# DC075B_CW_OUTPUTS.net
KiCad netlist of a schematic drawn in Altium Designer
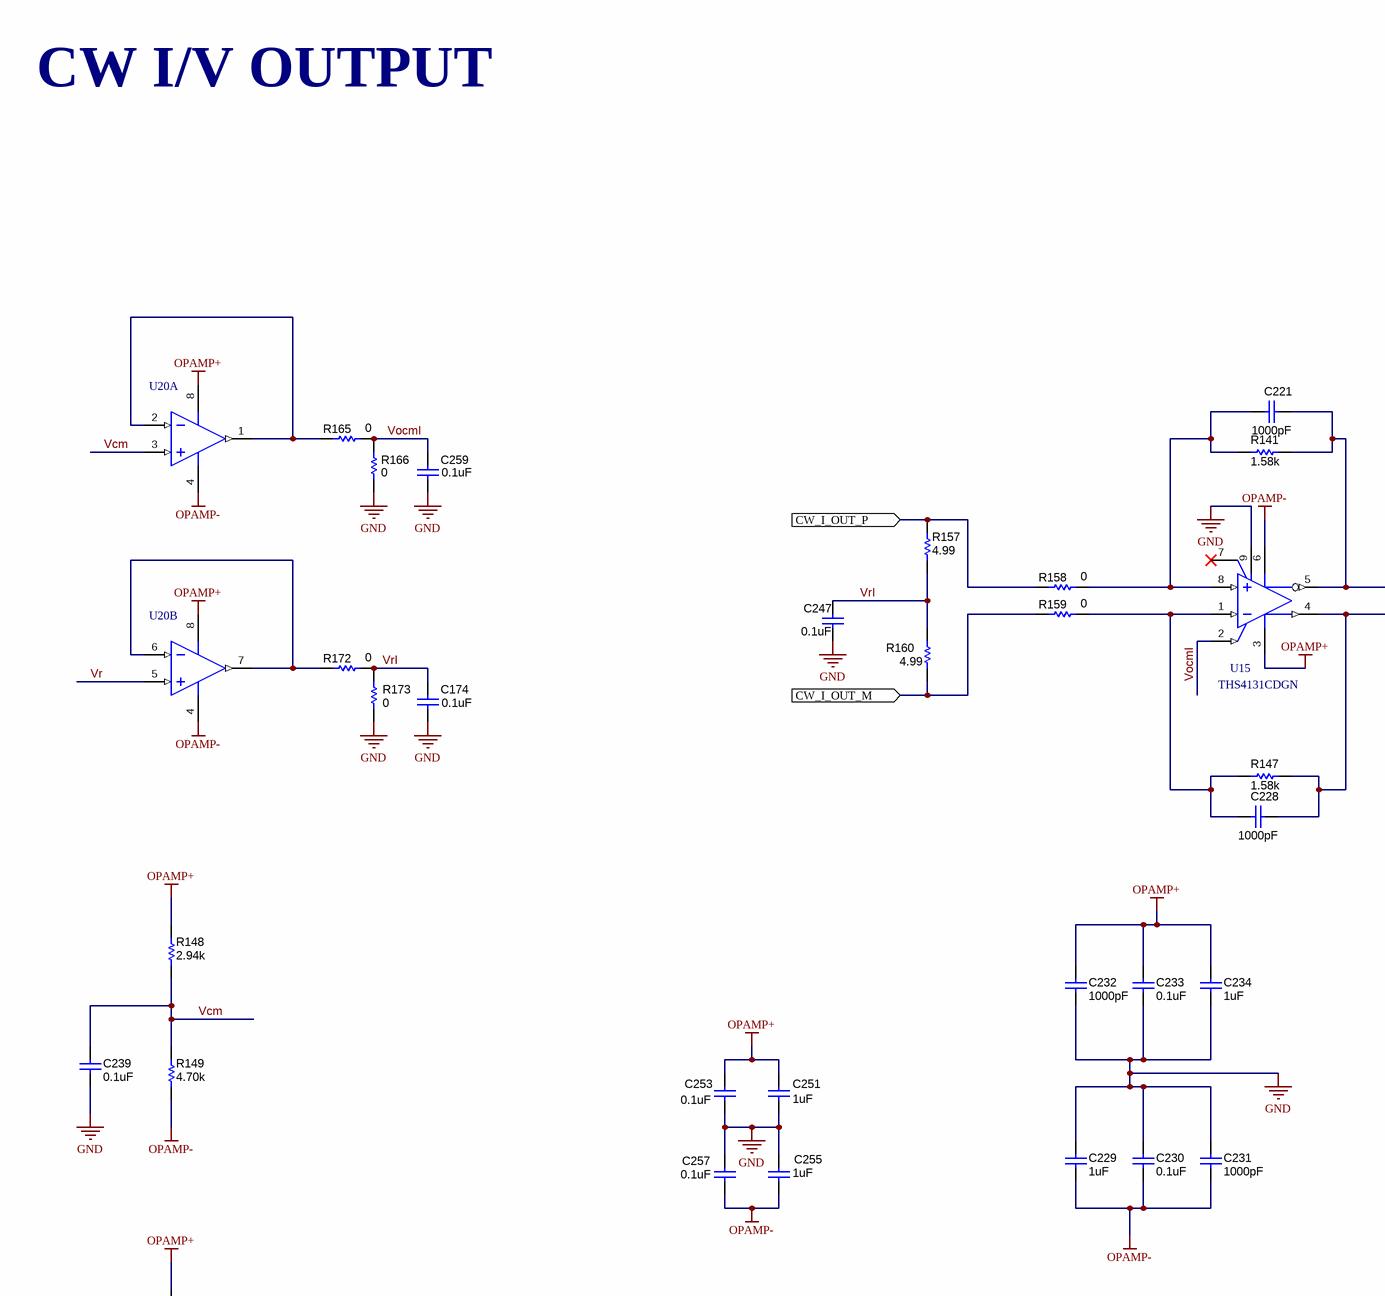
[diagram p0: DC075B_CW_OUTPUTS.SchDoc, top left]
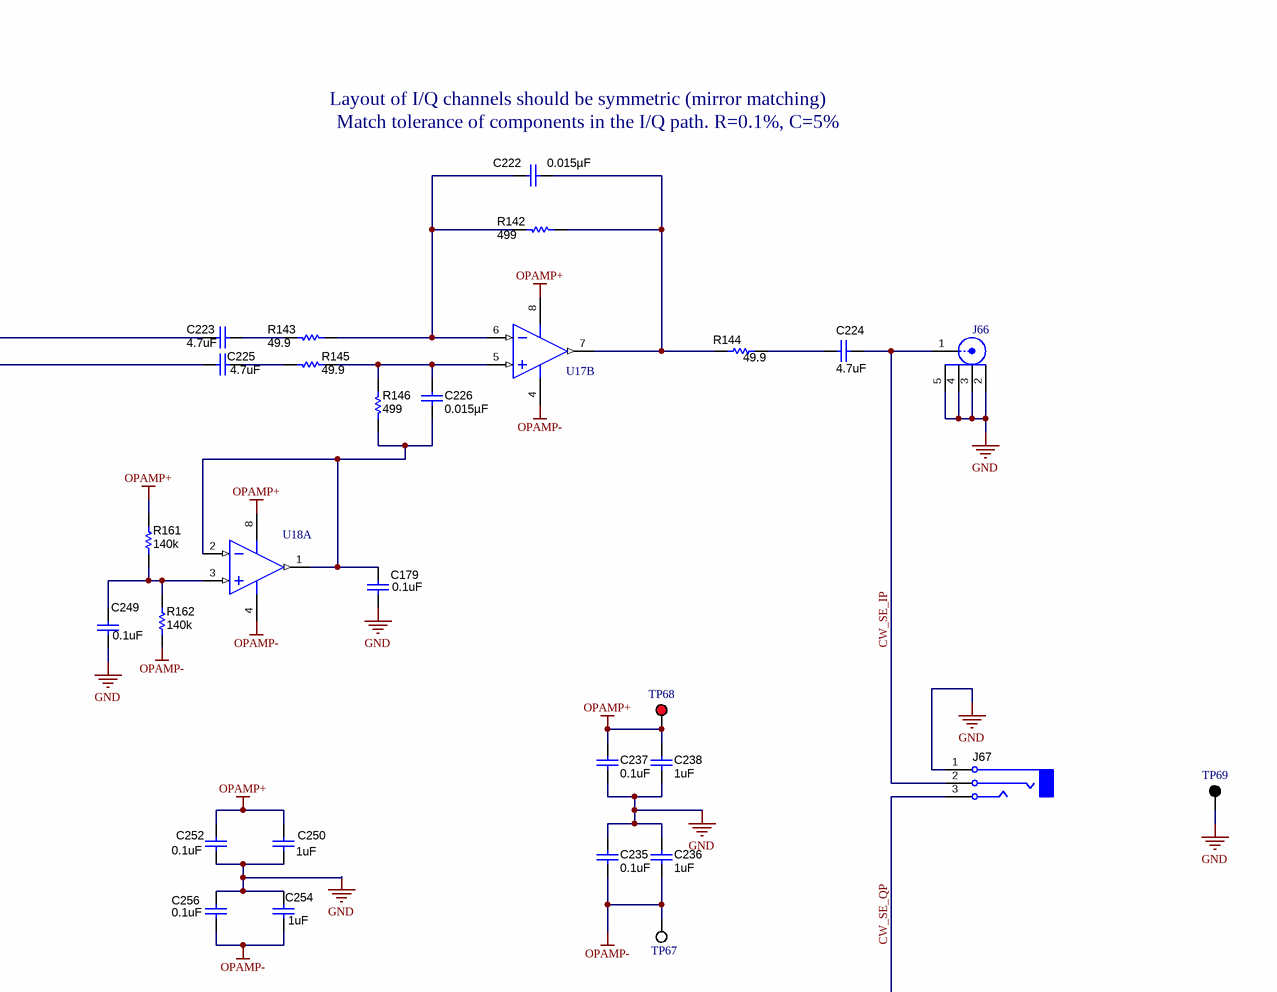
[diagram p1: DC075B_CW_OUTPUTS.SchDoc, top right]
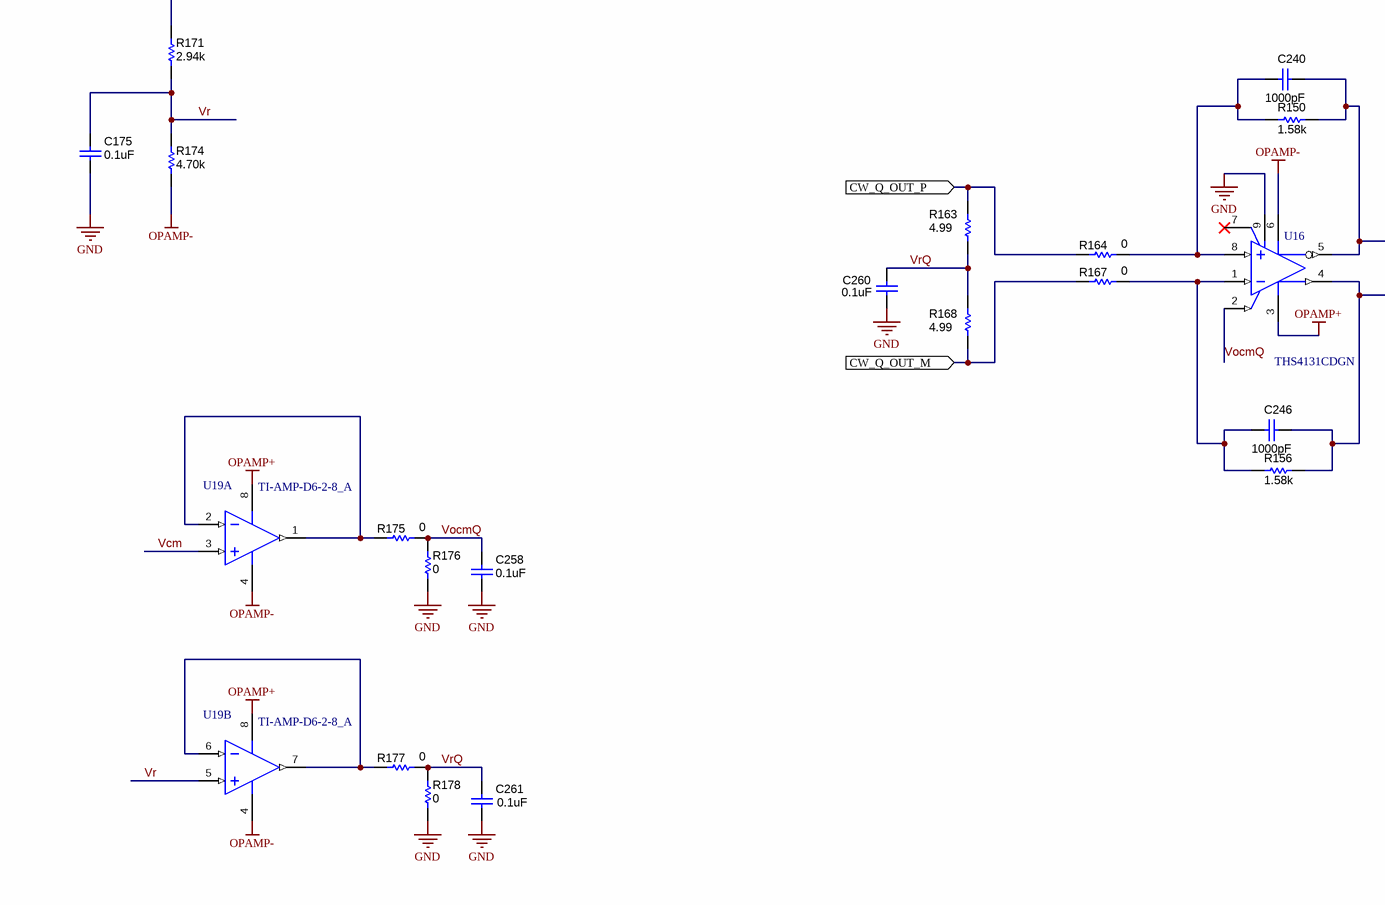
[diagram p2: DC075B_CW_OUTPUTS.SchDoc, bottom left]
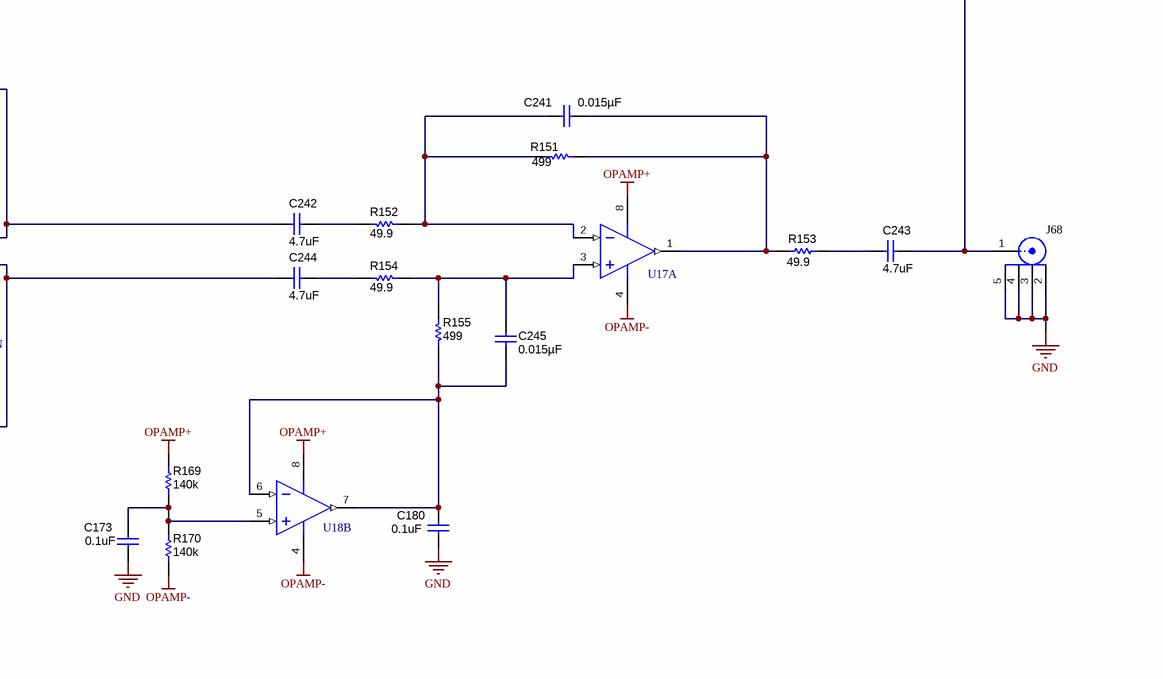
[diagram p3: DC075B_CW_OUTPUTS.SchDoc, bottom right]

(export (version "E")
  (design (tool "Eeschema 10.0.6"))
  (components
    (comp (ref "C173")
      (value "0.1uF")
      (footprint "0402")
      (description "CAP, CERM, 0.1 uF, 16 V, +/- 10%, X7R, 0402")
      (fields (field (name "PARTNUMBER") "GRM155R71C104KA88D") (field (name "MANUFACTURER") "MuRata"))
      (libsource (lib "Altium Vault - TI") (part "Capacitor"))
    )
    (comp (ref "C174")
      (value "0.1uF")
      (footprint "0402")
      (description "CAP, CERM, 0.1 uF, 16 V, +/- 10%, X7R, 0402")
      (fields (field (name "PARTNUMBER") "GRM155R71C104KA88D") (field (name "MANUFACTURER") "MuRata"))
      (libsource (lib "Altium Vault - TI") (part "Capacitor"))
    )
    (comp (ref "C175")
      (value "0.1uF")
      (footprint "0402")
      (description "CAP, CERM, 0.1 uF, 16 V, +/- 10%, X7R, 0402")
      (fields (field (name "PARTNUMBER") "GRM155R71C104KA88D") (field (name "MANUFACTURER") "MuRata"))
      (libsource (lib "Altium Vault - TI") (part "Capacitor"))
    )
    (comp (ref "C179")
      (value "0.1uF")
      (footprint "0402")
      (description "CAP, CERM, 0.1 uF, 16 V, +/- 10%, X7R, 0402")
      (fields (field (name "PARTNUMBER") "GRM155R71C104KA88D") (field (name "MANUFACTURER") "MuRata"))
      (libsource (lib "Altium Vault - TI") (part "Capacitor"))
    )
    (comp (ref "C180")
      (value "0.1uF")
      (footprint "0402")
      (description "CAP, CERM, 0.1 uF, 16 V, +/- 10%, X7R, 0402")
      (fields (field (name "PARTNUMBER") "GRM155R71C104KA88D") (field (name "MANUFACTURER") "MuRata"))
      (libsource (lib "Altium Vault - TI") (part "Capacitor"))
    )
    (comp (ref "C221")
      (value "885012205044")
      (footprint "0402")
      (description "CAP, CERM, 1000 pF, 25 V, +/- 10%, X7R, 0402")
      (fields (field (name "MANUFACTURER") "Wurth Elektronik") (field (name "VALUEDISPLAYED") "1000pF"))
      (libsource (lib "Altium Vault - TI") (part "CMP-0006229-2"))
    )
    (comp (ref "C222")
      (value "C0402C153J4RAC7867")
      (footprint "0402")
      (description "CAP, CERM, 0.015 µF, 16 V,+/- 5%, X7R, 0402")
      (fields (field (name "VALUEDISPLAYED") "0.015µF") (field (name "MANUFACTURER") "Kemet"))
      (libsource (lib "Altium Vault - TI") (part "Capacitor"))
    )
    (comp (ref "C223")
      (value "Capacitor")
      (footprint "0603")
      (description "CAP, CERM, 4.7 uF, 10 V, +/- 10%, X5R, 0603")
      (fields
        (field (name "PARTNUMBER") "C0603C475K8PACTU")
        (field (name "VALUEDISPLAYED") "4.7uF")
        (field (name "MANUFACTURER") "Kemet")
      )
      (libsource (lib "Altium Vault - TI") (part "Capacitor"))
    )
    (comp (ref "C224")
      (value "Capacitor")
      (footprint "0603")
      (description "CAP, CERM, 4.7 uF, 10 V, +/- 10%, X5R, 0603")
      (fields
        (field (name "PARTNUMBER") "C0603C475K8PACTU")
        (field (name "VALUEDISPLAYED") "4.7uF")
        (field (name "MANUFACTURER") "Kemet")
      )
      (libsource (lib "Altium Vault - TI") (part "Capacitor"))
    )
    (comp (ref "C225")
      (value "Capacitor")
      (footprint "0603")
      (description "CAP, CERM, 4.7 uF, 10 V, +/- 10%, X5R, 0603")
      (fields
        (field (name "PARTNUMBER") "C0603C475K8PACTU")
        (field (name "VALUEDISPLAYED") "4.7uF")
        (field (name "MANUFACTURER") "Kemet")
      )
      (libsource (lib "Altium Vault - TI") (part "Capacitor"))
    )
    (comp (ref "C226")
      (value "C0402C153J4RAC7867")
      (footprint "0402")
      (description "CAP, CERM, 0.015 µF, 16 V,+/- 5%, X7R, 0402")
      (fields (field (name "VALUEDISPLAYED") "0.015µF") (field (name "MANUFACTURER") "Kemet"))
      (libsource (lib "Altium Vault - TI") (part "Capacitor"))
    )
    (comp (ref "C228")
      (value "885012205044")
      (footprint "0402")
      (description "CAP, CERM, 1000 pF, 25 V, +/- 10%, X7R, 0402")
      (fields (field (name "MANUFACTURER") "Wurth Elektronik") (field (name "VALUEDISPLAYED") "1000pF"))
      (libsource (lib "Altium Vault - TI") (part "CMP-0006229-2"))
    )
    (comp (ref "C229")
      (value "1uF")
      (footprint "0603_HV")
      (description "CAP, CERM, 1 uF, 16 V, +/- 10%, X5R, 0603")
      (fields (field (name "PARTNUMBER") "C0603C105K4PACTU") (field (name "MANUFACTURER") "Kemet"))
      (libsource (lib "Altium Vault - TI") (part "Capacitor"))
    )
    (comp (ref "C230")
      (value "0.1uF")
      (footprint "0402")
      (description "CAP, CERM, 0.1 uF, 16 V, +/- 10%, X7R, 0402")
      (fields (field (name "PARTNUMBER") "GRM155R71C104KA88D") (field (name "MANUFACTURER") "MuRata"))
      (libsource (lib "Altium Vault - TI") (part "Capacitor"))
    )
    (comp (ref "C231")
      (value "885012205044")
      (footprint "0402")
      (description "CAP, CERM, 1000 pF, 25 V, +/- 10%, X7R, 0402")
      (fields (field (name "MANUFACTURER") "Wurth Elektronik") (field (name "VALUEDISPLAYED") "1000pF"))
      (libsource (lib "Altium Vault - TI") (part "CMP-0006229-2"))
    )
    (comp (ref "C232")
      (value "885012205044")
      (footprint "0402")
      (description "CAP, CERM, 1000 pF, 25 V, +/- 10%, X7R, 0402")
      (fields (field (name "MANUFACTURER") "Wurth Elektronik") (field (name "VALUEDISPLAYED") "1000pF"))
      (libsource (lib "Altium Vault - TI") (part "CMP-0006229-2"))
    )
    (comp (ref "C233")
      (value "0.1uF")
      (footprint "0402")
      (description "CAP, CERM, 0.1 uF, 16 V, +/- 10%, X7R, 0402")
      (fields (field (name "PARTNUMBER") "GRM155R71C104KA88D") (field (name "MANUFACTURER") "MuRata"))
      (libsource (lib "Altium Vault - TI") (part "Capacitor"))
    )
    (comp (ref "C234")
      (value "1uF")
      (footprint "0603_HV")
      (description "CAP, CERM, 1 uF, 16 V, +/- 10%, X5R, 0603")
      (fields (field (name "PARTNUMBER") "C0603C105K4PACTU") (field (name "MANUFACTURER") "Kemet"))
      (libsource (lib "Altium Vault - TI") (part "Capacitor"))
    )
    (comp (ref "C235")
      (value "0.1uF")
      (footprint "0402")
      (description "CAP, CERM, 0.1 uF, 16 V, +/- 10%, X7R, 0402")
      (fields (field (name "PARTNUMBER") "GRM155R71C104KA88D") (field (name "MANUFACTURER") "MuRata"))
      (libsource (lib "Altium Vault - TI") (part "Capacitor"))
    )
    (comp (ref "C236")
      (value "1uF")
      (footprint "0603_HV")
      (description "CAP, CERM, 1 uF, 16 V, +/- 10%, X5R, 0603")
      (fields (field (name "PARTNUMBER") "C0603C105K4PACTU") (field (name "MANUFACTURER") "Kemet"))
      (libsource (lib "Altium Vault - TI") (part "Capacitor"))
    )
    (comp (ref "C237")
      (value "0.1uF")
      (footprint "0402")
      (description "CAP, CERM, 0.1 uF, 16 V, +/- 10%, X7R, 0402")
      (fields (field (name "PARTNUMBER") "GRM155R71C104KA88D") (field (name "MANUFACTURER") "MuRata"))
      (libsource (lib "Altium Vault - TI") (part "Capacitor"))
    )
    (comp (ref "C238")
      (value "1uF")
      (footprint "0603_HV")
      (description "CAP, CERM, 1 uF, 16 V, +/- 10%, X5R, 0603")
      (fields (field (name "PARTNUMBER") "C0603C105K4PACTU") (field (name "MANUFACTURER") "Kemet"))
      (libsource (lib "Altium Vault - TI") (part "Capacitor"))
    )
    (comp (ref "C239")
      (value "0.1uF")
      (footprint "0402")
      (description "CAP, CERM, 0.1 uF, 16 V, +/- 10%, X7R, 0402")
      (fields (field (name "PARTNUMBER") "GRM155R71C104KA88D") (field (name "MANUFACTURER") "MuRata"))
      (libsource (lib "Altium Vault - TI") (part "Capacitor"))
    )
    (comp (ref "C240")
      (value "885012205044")
      (footprint "0402")
      (description "CAP, CERM, 1000 pF, 25 V, +/- 10%, X7R, 0402")
      (fields (field (name "MANUFACTURER") "Wurth Elektronik") (field (name "VALUEDISPLAYED") "1000pF"))
      (libsource (lib "Altium Vault - TI") (part "CMP-0006229-2"))
    )
    (comp (ref "C241")
      (value "C0402C153J4RAC7867")
      (footprint "0402")
      (description "CAP, CERM, 0.015 µF, 16 V,+/- 5%, X7R, 0402")
      (fields (field (name "VALUEDISPLAYED") "0.015µF") (field (name "MANUFACTURER") "Kemet"))
      (libsource (lib "Altium Vault - TI") (part "Capacitor"))
    )
    (comp (ref "C242")
      (value "Capacitor")
      (footprint "0603")
      (description "CAP, CERM, 4.7 uF, 10 V, +/- 10%, X5R, 0603")
      (fields
        (field (name "PARTNUMBER") "C0603C475K8PACTU")
        (field (name "VALUEDISPLAYED") "4.7uF")
        (field (name "MANUFACTURER") "Kemet")
      )
      (libsource (lib "Altium Vault - TI") (part "Capacitor"))
    )
    (comp (ref "C243")
      (value "Capacitor")
      (footprint "0603")
      (description "CAP, CERM, 4.7 uF, 10 V, +/- 10%, X5R, 0603")
      (fields
        (field (name "PARTNUMBER") "C0603C475K8PACTU")
        (field (name "VALUEDISPLAYED") "4.7uF")
        (field (name "MANUFACTURER") "Kemet")
      )
      (libsource (lib "Altium Vault - TI") (part "Capacitor"))
    )
    (comp (ref "C244")
      (value "Capacitor")
      (footprint "0603")
      (description "CAP, CERM, 4.7 uF, 10 V, +/- 10%, X5R, 0603")
      (fields
        (field (name "PARTNUMBER") "C0603C475K8PACTU")
        (field (name "VALUEDISPLAYED") "4.7uF")
        (field (name "MANUFACTURER") "Kemet")
      )
      (libsource (lib "Altium Vault - TI") (part "Capacitor"))
    )
    (comp (ref "C245")
      (value "C0402C153J4RAC7867")
      (footprint "0402")
      (description "CAP, CERM, 0.015 µF, 16 V,+/- 5%, X7R, 0402")
      (fields (field (name "VALUEDISPLAYED") "0.015µF") (field (name "MANUFACTURER") "Kemet"))
      (libsource (lib "Altium Vault - TI") (part "Capacitor"))
    )
    (comp (ref "C246")
      (value "885012205044")
      (footprint "0402")
      (description "CAP, CERM, 1000 pF, 25 V, +/- 10%, X7R, 0402")
      (fields (field (name "MANUFACTURER") "Wurth Elektronik") (field (name "VALUEDISPLAYED") "1000pF"))
      (libsource (lib "Altium Vault - TI") (part "CMP-0006229-2"))
    )
    (comp (ref "C247")
      (value "0.1uF")
      (footprint "0402")
      (description "CAP, CERM, 0.1 uF, 16 V, +/- 10%, X7R, 0402")
      (fields (field (name "PARTNUMBER") "GRM155R71C104KA88D") (field (name "MANUFACTURER") "MuRata"))
      (libsource (lib "Altium Vault - TI") (part "Capacitor"))
    )
    (comp (ref "C249")
      (value "0.1uF")
      (footprint "0402")
      (description "CAP, CERM, 0.1 uF, 16 V, +/- 10%, X7R, 0402")
      (fields (field (name "PARTNUMBER") "GRM155R71C104KA88D") (field (name "MANUFACTURER") "MuRata"))
      (libsource (lib "Altium Vault - TI") (part "Capacitor"))
    )
    (comp (ref "C250")
      (value "1uF")
      (footprint "0603_HV")
      (description "CAP, CERM, 1 uF, 16 V, +/- 10%, X5R, 0603")
      (fields (field (name "PARTNUMBER") "C0603C105K4PACTU") (field (name "MANUFACTURER") "Kemet"))
      (libsource (lib "Altium Vault - TI") (part "Capacitor"))
    )
    (comp (ref "C251")
      (value "1uF")
      (footprint "0603_HV")
      (description "CAP, CERM, 1 uF, 16 V, +/- 10%, X5R, 0603")
      (fields (field (name "PARTNUMBER") "C0603C105K4PACTU") (field (name "MANUFACTURER") "Kemet"))
      (libsource (lib "Altium Vault - TI") (part "Capacitor"))
    )
    (comp (ref "C252")
      (value "0.1uF")
      (footprint "0402")
      (description "CAP, CERM, 0.1 uF, 16 V, +/- 10%, X7R, 0402")
      (fields (field (name "PARTNUMBER") "GRM155R71C104KA88D") (field (name "MANUFACTURER") "MuRata"))
      (libsource (lib "Altium Vault - TI") (part "Capacitor"))
    )
    (comp (ref "C253")
      (value "0.1uF")
      (footprint "0402")
      (description "CAP, CERM, 0.1 uF, 16 V, +/- 10%, X7R, 0402")
      (fields (field (name "PARTNUMBER") "GRM155R71C104KA88D") (field (name "MANUFACTURER") "MuRata"))
      (libsource (lib "Altium Vault - TI") (part "Capacitor"))
    )
    (comp (ref "C254")
      (value "1uF")
      (footprint "0603_HV")
      (description "CAP, CERM, 1 uF, 16 V, +/- 10%, X5R, 0603")
      (fields (field (name "PARTNUMBER") "C0603C105K4PACTU") (field (name "MANUFACTURER") "Kemet"))
      (libsource (lib "Altium Vault - TI") (part "Capacitor"))
    )
    (comp (ref "C255")
      (value "1uF")
      (footprint "0603_HV")
      (description "CAP, CERM, 1 uF, 16 V, +/- 10%, X5R, 0603")
      (fields (field (name "PARTNUMBER") "C0603C105K4PACTU") (field (name "MANUFACTURER") "Kemet"))
      (libsource (lib "Altium Vault - TI") (part "Capacitor"))
    )
    (comp (ref "C256")
      (value "0.1uF")
      (footprint "0402")
      (description "CAP, CERM, 0.1 uF, 16 V, +/- 10%, X7R, 0402")
      (fields (field (name "PARTNUMBER") "GRM155R71C104KA88D") (field (name "MANUFACTURER") "MuRata"))
      (libsource (lib "Altium Vault - TI") (part "Capacitor"))
    )
    (comp (ref "C257")
      (value "0.1uF")
      (footprint "0402")
      (description "CAP, CERM, 0.1 uF, 16 V, +/- 10%, X7R, 0402")
      (fields (field (name "PARTNUMBER") "GRM155R71C104KA88D") (field (name "MANUFACTURER") "MuRata"))
      (libsource (lib "Altium Vault - TI") (part "Capacitor"))
    )
    (comp (ref "C258")
      (value "0.1uF")
      (footprint "0402")
      (description "CAP, CERM, 0.1 uF, 16 V, +/- 10%, X7R, 0402")
      (fields (field (name "PARTNUMBER") "GRM155R71C104KA88D") (field (name "MANUFACTURER") "MuRata"))
      (libsource (lib "Altium Vault - TI") (part "Capacitor"))
    )
    (comp (ref "C259")
      (value "0.1uF")
      (footprint "0402")
      (description "CAP, CERM, 0.1 uF, 16 V, +/- 10%, X7R, 0402")
      (fields (field (name "PARTNUMBER") "GRM155R71C104KA88D") (field (name "MANUFACTURER") "MuRata"))
      (libsource (lib "Altium Vault - TI") (part "Capacitor"))
    )
    (comp (ref "C260")
      (value "0.1uF")
      (footprint "0402")
      (description "CAP, CERM, 0.1 uF, 16 V, +/- 10%, X7R, 0402")
      (fields (field (name "PARTNUMBER") "GRM155R71C104KA88D") (field (name "MANUFACTURER") "MuRata"))
      (libsource (lib "Altium Vault - TI") (part "Capacitor"))
    )
    (comp (ref "C261")
      (value "0.1uF")
      (footprint "0402")
      (description "CAP, CERM, 0.1 uF, 16 V, +/- 10%, X7R, 0402")
      (fields (field (name "PARTNUMBER") "GRM155R71C104KA88D") (field (name "MANUFACTURER") "MuRata"))
      (libsource (lib "Altium Vault - TI") (part "Capacitor"))
    )
    (comp (ref "J66")
      (value "5-1814832-1")
      (footprint "TE_5-1814832-1")
      (description "SMA Straight PCB Socket Die Cast, 50 Ohm, TH")
      (fields (field (name "MANUFACTURER") "TE Connectivity"))
      (libsource (lib "Altium Vault - TI") (part "SMA_Contact1_GND2345"))
    )
    (comp (ref "J67")
      (value "Audio_T3R2S1")
      (footprint "KYCON_STX-3000")
      (description "Audio Jack, 3.5 mm, Stereo, R/A, TH")
      (fields (field (name "PARTNUMBER") "STX-3000") (field (name "MANUFACTURER") "Kycon Inc"))
      (libsource (lib "Altium Vault - TI") (part "CMP-0075053-1"))
    )
    (comp (ref "J68")
      (value "5-1814832-1")
      (footprint "TE_5-1814832-1")
      (description "SMA Straight PCB Socket Die Cast, 50 Ohm, TH")
      (fields (field (name "MANUFACTURER") "TE Connectivity"))
      (libsource (lib "Altium Vault - TI") (part "SMA_Contact1_GND2345"))
    )
    (comp (ref "R141")
      (value "CRCW04021K58FKED")
      (footprint "0402")
      (description "RES, 1.58 k, 1%, 0.063 W, AEC-Q200 Grade 0, 0402")
      (fields (field (name "MANUFACTURER") "Vishay-Dale") (field (name "VALUEDISPLAYED") "1.58k"))
      (libsource (lib "Altium Vault - TI") (part "Resistor"))
    )
    (comp (ref "R142")
      (value "Resistor")
      (footprint "0402")
      (description "RES, 499, 1%, 0.063 W, AEC-Q200 Grade 0, 0402")
      (fields
        (field (name "PARTNUMBER") "CRCW0402499RFKED")
        (field (name "VALUEDISPLAYED") "499")
        (field (name "MANUFACTURER") "Vishay-Dale")
      )
      (libsource (lib "Altium Vault - TI") (part "Resistor"))
    )
    (comp (ref "R143")
      (value "Resistor")
      (footprint "0402")
      (description "RES, 49.9, 1%, 0.063 W, AEC-Q200 Grade 0, 0402")
      (fields
        (field (name "PARTNUMBER") "CRCW040249R9FKED")
        (field (name "VALUEDISPLAYED") "49.9")
        (field (name "MANUFACTURER") "Vishay-Dale")
      )
      (libsource (lib "Altium Vault - TI") (part "Resistor"))
    )
    (comp (ref "R144")
      (value "49.9")
      (footprint "0402")
      (description "RES, 49.9, 1%, 0.063 W, AEC-Q200 Grade 0, 0402")
      (fields (field (name "MANUFACTURER") "Vishay-Dale") (field (name "PARTNUMBER") "CRCW040249R9FKED"))
      (libsource (lib "Altium Vault - TI") (part "Resistor"))
    )
    (comp (ref "R145")
      (value "Resistor")
      (footprint "0402")
      (description "RES, 49.9, 1%, 0.063 W, AEC-Q200 Grade 0, 0402")
      (fields
        (field (name "PARTNUMBER") "CRCW040249R9FKED")
        (field (name "VALUEDISPLAYED") "49.9")
        (field (name "MANUFACTURER") "Vishay-Dale")
      )
      (libsource (lib "Altium Vault - TI") (part "Resistor"))
    )
    (comp (ref "R146")
      (value "Resistor")
      (footprint "0402")
      (description "RES, 499, 1%, 0.063 W, AEC-Q200 Grade 0, 0402")
      (fields
        (field (name "PARTNUMBER") "CRCW0402499RFKED")
        (field (name "VALUEDISPLAYED") "499")
        (field (name "MANUFACTURER") "Vishay-Dale")
      )
      (libsource (lib "Altium Vault - TI") (part "Resistor"))
    )
    (comp (ref "R147")
      (value "CRCW04021K58FKED")
      (footprint "0402")
      (description "RES, 1.58 k, 1%, 0.063 W, AEC-Q200 Grade 0, 0402")
      (fields (field (name "MANUFACTURER") "Vishay-Dale") (field (name "VALUEDISPLAYED") "1.58k"))
      (libsource (lib "Altium Vault - TI") (part "Resistor"))
    )
    (comp (ref "R148")
      (value "CRCW04022K94FKED")
      (footprint "0402")
      (description "RES, 2.94 k, 1%, 0.063 W, AEC-Q200 Grade 0, 0402")
      (fields (field (name "MANUFACTURER") "Vishay-Dale") (field (name "VALUEDISPLAYED") "2.94k"))
      (libsource (lib "Altium Vault - TI") (part "Resistor"))
    )
    (comp (ref "R149")
      (value "Resistor")
      (footprint "0402")
      (description "RES, 4.70 k, 1%, 0.1 W, 0402")
      (fields
        (field (name "PARTNUMBER") "ERJ-2RKF4701X")
        (field (name "VALUEDISPLAYED") "4.70k")
        (field (name "MANUFACTURER") "Panasonic")
      )
      (libsource (lib "Altium Vault - TI") (part "Resistor"))
    )
    (comp (ref "R150")
      (value "CRCW04021K58FKED")
      (footprint "0402")
      (description "RES, 1.58 k, 1%, 0.063 W, AEC-Q200 Grade 0, 0402")
      (fields (field (name "MANUFACTURER") "Vishay-Dale") (field (name "VALUEDISPLAYED") "1.58k"))
      (libsource (lib "Altium Vault - TI") (part "Resistor"))
    )
    (comp (ref "R151")
      (value "Resistor")
      (footprint "0402")
      (description "RES, 499, 1%, 0.063 W, AEC-Q200 Grade 0, 0402")
      (fields
        (field (name "PARTNUMBER") "CRCW0402499RFKED")
        (field (name "VALUEDISPLAYED") "499")
        (field (name "MANUFACTURER") "Vishay-Dale")
      )
      (libsource (lib "Altium Vault - TI") (part "Resistor"))
    )
    (comp (ref "R152")
      (value "Resistor")
      (footprint "0402")
      (description "RES, 49.9, 1%, 0.063 W, AEC-Q200 Grade 0, 0402")
      (fields
        (field (name "PARTNUMBER") "CRCW040249R9FKED")
        (field (name "VALUEDISPLAYED") "49.9")
        (field (name "MANUFACTURER") "Vishay-Dale")
      )
      (libsource (lib "Altium Vault - TI") (part "Resistor"))
    )
    (comp (ref "R153")
      (value "49.9")
      (footprint "0402")
      (description "RES, 49.9, 1%, 0.063 W, AEC-Q200 Grade 0, 0402")
      (fields (field (name "MANUFACTURER") "Vishay-Dale") (field (name "PARTNUMBER") "CRCW040249R9FKED"))
      (libsource (lib "Altium Vault - TI") (part "Resistor"))
    )
    (comp (ref "R154")
      (value "Resistor")
      (footprint "0402")
      (description "RES, 49.9, 1%, 0.063 W, AEC-Q200 Grade 0, 0402")
      (fields
        (field (name "PARTNUMBER") "CRCW040249R9FKED")
        (field (name "VALUEDISPLAYED") "49.9")
        (field (name "MANUFACTURER") "Vishay-Dale")
      )
      (libsource (lib "Altium Vault - TI") (part "Resistor"))
    )
    (comp (ref "R155")
      (value "Resistor")
      (footprint "0402")
      (description "RES, 499, 1%, 0.063 W, AEC-Q200 Grade 0, 0402")
      (fields
        (field (name "PARTNUMBER") "CRCW0402499RFKED")
        (field (name "VALUEDISPLAYED") "499")
        (field (name "MANUFACTURER") "Vishay-Dale")
      )
      (libsource (lib "Altium Vault - TI") (part "Resistor"))
    )
    (comp (ref "R156")
      (value "CRCW04021K58FKED")
      (footprint "0402")
      (description "RES, 1.58 k, 1%, 0.063 W, AEC-Q200 Grade 0, 0402")
      (fields (field (name "MANUFACTURER") "Vishay-Dale") (field (name "VALUEDISPLAYED") "1.58k"))
      (libsource (lib "Altium Vault - TI") (part "Resistor"))
    )
    (comp (ref "R157")
      (value "Resistor")
      (footprint "0402")
      (description "RES, 4.99, 1%, 0.063 W, AEC-Q200 Grade 0, 0402")
      (fields
        (field (name "PARTNUMBER") "CRCW04024R99FKED")
        (field (name "VALUEDISPLAYED") "4.99")
        (field (name "MANUFACTURER") "Vishay-Dale")
      )
      (libsource (lib "Altium Vault - TI") (part "Resistor"))
    )
    (comp (ref "R158")
      (value "0")
      (footprint "0402")
      (description "RES, 0, 5%, 0.063 W, AEC-Q200 Grade 0, 0402")
      (fields (field (name "MANUFACTURER") "Vishay-Dale") (field (name "PARTNUMBER") "CRCW04020000Z0ED"))
      (libsource (lib "Altium Vault - TI") (part "Resistor"))
    )
    (comp (ref "R159")
      (value "0")
      (footprint "0402")
      (description "RES, 0, 5%, 0.063 W, AEC-Q200 Grade 0, 0402")
      (fields (field (name "MANUFACTURER") "Vishay-Dale") (field (name "PARTNUMBER") "CRCW04020000Z0ED"))
      (libsource (lib "Altium Vault - TI") (part "Resistor"))
    )
    (comp (ref "R160")
      (value "Resistor")
      (footprint "0402")
      (description "RES, 4.99, 1%, 0.063 W, AEC-Q200 Grade 0, 0402")
      (fields
        (field (name "PARTNUMBER") "CRCW04024R99FKED")
        (field (name "VALUEDISPLAYED") "4.99")
        (field (name "MANUFACTURER") "Vishay-Dale")
      )
      (libsource (lib "Altium Vault - TI") (part "Resistor"))
    )
    (comp (ref "R161")
      (value "Resistor")
      (footprint "0402")
      (description "RES, 140 k, 1%, 0.063 W, AEC-Q200 Grade 0, 0402")
      (fields
        (field (name "PARTNUMBER") "CRCW0402140KFKED")
        (field (name "VALUEDISPLAYED") "140k")
        (field (name "MANUFACTURER") "Vishay-Dale")
      )
      (libsource (lib "Altium Vault - TI") (part "Resistor"))
    )
    (comp (ref "R162")
      (value "Resistor")
      (footprint "0402")
      (description "RES, 140 k, 1%, 0.063 W, AEC-Q200 Grade 0, 0402")
      (fields
        (field (name "PARTNUMBER") "CRCW0402140KFKED")
        (field (name "VALUEDISPLAYED") "140k")
        (field (name "MANUFACTURER") "Vishay-Dale")
      )
      (libsource (lib "Altium Vault - TI") (part "Resistor"))
    )
    (comp (ref "R163")
      (value "Resistor")
      (footprint "0402")
      (description "RES, 4.99, 1%, 0.063 W, AEC-Q200 Grade 0, 0402")
      (fields
        (field (name "PARTNUMBER") "CRCW04024R99FKED")
        (field (name "VALUEDISPLAYED") "4.99")
        (field (name "MANUFACTURER") "Vishay-Dale")
      )
      (libsource (lib "Altium Vault - TI") (part "Resistor"))
    )
    (comp (ref "R164")
      (value "0")
      (footprint "0402")
      (description "RES, 0, 5%, 0.063 W, AEC-Q200 Grade 0, 0402")
      (fields (field (name "MANUFACTURER") "Vishay-Dale") (field (name "PARTNUMBER") "CRCW04020000Z0ED"))
      (libsource (lib "Altium Vault - TI") (part "Resistor"))
    )
    (comp (ref "R165")
      (value "0")
      (footprint "0402")
      (description "RES, 0, 5%, 0.063 W, AEC-Q200 Grade 0, 0402")
      (fields (field (name "MANUFACTURER") "Vishay-Dale") (field (name "PARTNUMBER") "CRCW04020000Z0ED"))
      (libsource (lib "Altium Vault - TI") (part "Resistor"))
    )
    (comp (ref "R166")
      (value "0")
      (footprint "0402")
      (description "RES, 0, 5%, 0.063 W, AEC-Q200 Grade 0, 0402")
      (fields (field (name "MANUFACTURER") "Vishay-Dale") (field (name "PARTNUMBER") "CRCW04020000Z0ED"))
      (libsource (lib "Altium Vault - TI") (part "Resistor"))
    )
    (comp (ref "R167")
      (value "0")
      (footprint "0402")
      (description "RES, 0, 5%, 0.063 W, AEC-Q200 Grade 0, 0402")
      (fields (field (name "MANUFACTURER") "Vishay-Dale") (field (name "PARTNUMBER") "CRCW04020000Z0ED"))
      (libsource (lib "Altium Vault - TI") (part "Resistor"))
    )
    (comp (ref "R168")
      (value "Resistor")
      (footprint "0402")
      (description "RES, 4.99, 1%, 0.063 W, AEC-Q200 Grade 0, 0402")
      (fields
        (field (name "PARTNUMBER") "CRCW04024R99FKED")
        (field (name "VALUEDISPLAYED") "4.99")
        (field (name "MANUFACTURER") "Vishay-Dale")
      )
      (libsource (lib "Altium Vault - TI") (part "Resistor"))
    )
    (comp (ref "R169")
      (value "Resistor")
      (footprint "0402")
      (description "RES, 140 k, 1%, 0.063 W, AEC-Q200 Grade 0, 0402")
      (fields
        (field (name "PARTNUMBER") "CRCW0402140KFKED")
        (field (name "VALUEDISPLAYED") "140k")
        (field (name "MANUFACTURER") "Vishay-Dale")
      )
      (libsource (lib "Altium Vault - TI") (part "Resistor"))
    )
    (comp (ref "R170")
      (value "Resistor")
      (footprint "0402")
      (description "RES, 140 k, 1%, 0.063 W, AEC-Q200 Grade 0, 0402")
      (fields
        (field (name "PARTNUMBER") "CRCW0402140KFKED")
        (field (name "VALUEDISPLAYED") "140k")
        (field (name "MANUFACTURER") "Vishay-Dale")
      )
      (libsource (lib "Altium Vault - TI") (part "Resistor"))
    )
    (comp (ref "R171")
      (value "CRCW04022K94FKED")
      (footprint "0402")
      (description "RES, 2.94 k, 1%, 0.063 W, AEC-Q200 Grade 0, 0402")
      (fields (field (name "MANUFACTURER") "Vishay-Dale") (field (name "VALUEDISPLAYED") "2.94k"))
      (libsource (lib "Altium Vault - TI") (part "Resistor"))
    )
    (comp (ref "R172")
      (value "0")
      (footprint "0402")
      (description "RES, 0, 5%, 0.063 W, AEC-Q200 Grade 0, 0402")
      (fields (field (name "MANUFACTURER") "Vishay-Dale") (field (name "PARTNUMBER") "CRCW04020000Z0ED"))
      (libsource (lib "Altium Vault - TI") (part "Resistor"))
    )
    (comp (ref "R173")
      (value "0")
      (footprint "0402")
      (description "RES, 0, 5%, 0.063 W, AEC-Q200 Grade 0, 0402")
      (fields (field (name "MANUFACTURER") "Vishay-Dale") (field (name "PARTNUMBER") "CRCW04020000Z0ED"))
      (libsource (lib "Altium Vault - TI") (part "Resistor"))
    )
    (comp (ref "R174")
      (value "Resistor")
      (footprint "0402")
      (description "RES, 4.70 k, 1%, 0.1 W, 0402")
      (fields
        (field (name "PARTNUMBER") "ERJ-2RKF4701X")
        (field (name "VALUEDISPLAYED") "4.70k")
        (field (name "MANUFACTURER") "Panasonic")
      )
      (libsource (lib "Altium Vault - TI") (part "Resistor"))
    )
    (comp (ref "R175")
      (value "0")
      (footprint "0402")
      (description "RES, 0, 5%, 0.063 W, AEC-Q200 Grade 0, 0402")
      (fields (field (name "MANUFACTURER") "Vishay-Dale") (field (name "PARTNUMBER") "CRCW04020000Z0ED"))
      (libsource (lib "Altium Vault - TI") (part "Resistor"))
    )
    (comp (ref "R176")
      (value "0")
      (footprint "0402")
      (description "RES, 0, 5%, 0.063 W, AEC-Q200 Grade 0, 0402")
      (fields (field (name "MANUFACTURER") "Vishay-Dale") (field (name "PARTNUMBER") "CRCW04020000Z0ED"))
      (libsource (lib "Altium Vault - TI") (part "Resistor"))
    )
    (comp (ref "R177")
      (value "0")
      (footprint "0402")
      (description "RES, 0, 5%, 0.063 W, AEC-Q200 Grade 0, 0402")
      (fields (field (name "MANUFACTURER") "Vishay-Dale") (field (name "PARTNUMBER") "CRCW04020000Z0ED"))
      (libsource (lib "Altium Vault - TI") (part "Resistor"))
    )
    (comp (ref "R178")
      (value "0")
      (footprint "0402")
      (description "RES, 0, 5%, 0.063 W, AEC-Q200 Grade 0, 0402")
      (fields (field (name "MANUFACTURER") "Vishay-Dale") (field (name "PARTNUMBER") "CRCW04020000Z0ED"))
      (libsource (lib "Altium Vault - TI") (part "Resistor"))
    )
    (comp (ref "TP67")
      (value "5002")
      (footprint "Keystone5002")
      (description "Test Point, Miniature, White, TH")
      (fields (field (name "MANUFACTURER") "Keystone"))
      (libsource (lib "Altium Vault - TI") (part "5002"))
    )
    (comp (ref "TP68")
      (value "5000")
      (footprint "Keystone5000")
      (description "Test Point, Miniature, Red, TH")
      (fields (field (name "MANUFACTURER") "Keystone"))
      (libsource (lib "Altium Vault - TI") (part "5000"))
    )
    (comp (ref "TP69")
      (value "5001")
      (footprint "Keystone5001")
      (description "Test Point, Miniature, Black, TH")
      (fields (field (name "MANUFACTURER") "Keystone"))
      (libsource (lib "Altium Vault - TI") (part "5001"))
    )
    (comp (ref "U15")
      (value "THS4131CDGN")
      (footprint "DGN0008D_N")
      (fields (field (name "PARTNUMBER") "THS4131CDGN") (field (name "MANUFACTURER") "Texas Instruments"))
      (libsource (lib "Altium Vault - TI") (part "TI-THS41X1DGN8-1760X1425TP"))
    )
    (comp (ref "U16")
      (value "THS4131CDGN")
      (footprint "DGN0008D_N")
      (fields (field (name "PARTNUMBER") "THS4131CDGN") (field (name "MANUFACTURER") "Texas Instruments"))
      (libsource (lib "Altium Vault - TI") (part "TI-THS41X1DGN8-1760X1425TP"))
    )
    (comp (ref "U17")
      (value "TI-AMP-D6-2-8_A")
      (footprint "D0008A_N")
      (fields (field (name "MANUFACTURER") "Texas Instruments") (field (name "PARTNUMBER") "OPA2614ID"))
      (libsource (lib "Altium Vault - TI") (part "TI-AMP-D6-2-8_A"))
    )
    (comp (ref "U18")
      (value "TI-AMP-D6-2-8_A")
      (footprint "D0008A_N")
      (fields (field (name "MANUFACTURER") "Texas Instruments") (field (name "PARTNUMBER") "OPA2614ID"))
      (libsource (lib "Altium Vault - TI") (part "TI-AMP-D6-2-8_A"))
    )
    (comp (ref "U19")
      (value "TI-AMP-D6-2-8_A")
      (footprint "D0008A_N")
      (fields (field (name "MANUFACTURER") "Texas Instruments") (field (name "PARTNUMBER") "OPA2614ID"))
      (libsource (lib "Altium Vault - TI") (part "TI-AMP-D6-2-8_A"))
    )
    (comp (ref "U20")
      (value "TI-AMP-D6-2-8_A")
      (footprint "D0008A_N")
      (fields (field (name "MANUFACTURER") "Texas Instruments") (field (name "PARTNUMBER") "OPA2614ID"))
      (libsource (lib "Altium Vault - TI") (part "TI-AMP-D6-2-8_A"))
    )
  )
  (nets
    (net (code "1") (name "/CW_I_OUT_M") (class "Default")
      (node (ref "R159") (pin "2") (pinfunction "2_2") (pintype "passive"))
      (node (ref "R160") (pin "1") (pinfunction "1_1") (pintype "passive"))
    )
    (net (code "2") (name "/CW_I_OUT_P") (class "Default")
      (node (ref "R157") (pin "2") (pinfunction "2_2") (pintype "passive"))
      (node (ref "R158") (pin "2") (pinfunction "2_2") (pintype "passive"))
    )
    (net (code "3") (name "/CW_Q_OUT_M") (class "Default")
      (node (ref "R167") (pin "2") (pinfunction "2_2") (pintype "passive"))
      (node (ref "R168") (pin "1") (pinfunction "1_1") (pintype "passive"))
    )
    (net (code "4") (name "/CW_Q_OUT_P") (class "Default")
      (node (ref "R163") (pin "2") (pinfunction "2_2") (pintype "passive"))
      (node (ref "R164") (pin "2") (pinfunction "2_2") (pintype "passive"))
    )
    (net (code "5") (name "/CW_SE_IP") (class "Default")
      (node (ref "C224") (pin "1") (pinfunction "1_1") (pintype "passive"))
      (node (ref "J66") (pin "1") (pinfunction "1_1") (pintype "passive"))
      (node (ref "J67") (pin "2") (pinfunction "TIP_2") (pintype "passive"))
    )
    (net (code "6") (name "/CW_SE_QP") (class "Default")
      (node (ref "C243") (pin "1") (pinfunction "1_1") (pintype "passive"))
      (node (ref "J67") (pin "3") (pinfunction "RING_3") (pintype "passive"))
      (node (ref "J68") (pin "1") (pinfunction "1_1") (pintype "passive"))
    )
    (net (code "7") (name "/Vcm") (class "Default")
      (node (ref "C239") (pin "2") (pinfunction "2_2") (pintype "passive"))
      (node (ref "R148") (pin "1") (pinfunction "1_1") (pintype "passive"))
      (node (ref "R149") (pin "2") (pinfunction "2_2") (pintype "passive"))
      (node (ref "U19") (pin "3") (pinfunction "IN_A+_3") (pintype "input"))
      (node (ref "U20") (pin "3") (pinfunction "IN_A+_3") (pintype "input"))
    )
    (net (code "8") (name "/VocmI") (class "Default")
      (node (ref "C259") (pin "1") (pinfunction "1_1") (pintype "passive"))
      (node (ref "R165") (pin "1") (pinfunction "1_1") (pintype "passive"))
      (node (ref "R166") (pin "1") (pinfunction "1_1") (pintype "passive"))
      (node (ref "U15") (pin "2") (pinfunction "VOCM_2") (pintype "input"))
    )
    (net (code "9") (name "/VocmQ") (class "Default")
      (node (ref "C258") (pin "1") (pinfunction "1_1") (pintype "passive"))
      (node (ref "R175") (pin "1") (pinfunction "1_1") (pintype "passive"))
      (node (ref "R176") (pin "1") (pinfunction "1_1") (pintype "passive"))
      (node (ref "U16") (pin "2") (pinfunction "VOCM_2") (pintype "input"))
    )
    (net (code "10") (name "/Vr") (class "Default")
      (node (ref "C175") (pin "2") (pinfunction "2_2") (pintype "passive"))
      (node (ref "R171") (pin "1") (pinfunction "1_1") (pintype "passive"))
      (node (ref "R174") (pin "2") (pinfunction "2_2") (pintype "passive"))
      (node (ref "U19") (pin "5") (pinfunction "IN_B+_5") (pintype "input"))
      (node (ref "U20") (pin "5") (pinfunction "IN_B+_5") (pintype "input"))
    )
    (net (code "11") (name "/VrI") (class "Default")
      (node (ref "C174") (pin "1") (pinfunction "1_1") (pintype "passive"))
      (node (ref "C247") (pin "1") (pinfunction "1_1") (pintype "passive"))
      (node (ref "R157") (pin "1") (pinfunction "1_1") (pintype "passive"))
      (node (ref "R160") (pin "2") (pinfunction "2_2") (pintype "passive"))
      (node (ref "R172") (pin "1") (pinfunction "1_1") (pintype "passive"))
      (node (ref "R173") (pin "1") (pinfunction "1_1") (pintype "passive"))
    )
    (net (code "12") (name "/VrQ") (class "Default")
      (node (ref "C260") (pin "1") (pinfunction "1_1") (pintype "passive"))
      (node (ref "C261") (pin "1") (pinfunction "1_1") (pintype "passive"))
      (node (ref "R163") (pin "1") (pinfunction "1_1") (pintype "passive"))
      (node (ref "R168") (pin "2") (pinfunction "2_2") (pintype "passive"))
      (node (ref "R177") (pin "1") (pinfunction "1_1") (pintype "passive"))
      (node (ref "R178") (pin "1") (pinfunction "1_1") (pintype "passive"))
    )
    (net (code "13") (name "GND") (class "Default")
      (node (ref "C173") (pin "1") (pinfunction "1_1") (pintype "passive"))
      (node (ref "C174") (pin "2") (pinfunction "2_2") (pintype "passive"))
      (node (ref "C175") (pin "1") (pinfunction "1_1") (pintype "passive"))
      (node (ref "C179") (pin "2") (pinfunction "2_2") (pintype "passive"))
      (node (ref "C180") (pin "2") (pinfunction "2_2") (pintype "passive"))
      (node (ref "C229") (pin "1") (pinfunction "1_1") (pintype "passive"))
      (node (ref "C230") (pin "1") (pinfunction "1_1") (pintype "passive"))
      (node (ref "C231") (pin "2") (pinfunction "2_2") (pintype "passive"))
      (node (ref "C232") (pin "2") (pinfunction "2_2") (pintype "passive"))
      (node (ref "C233") (pin "1") (pinfunction "1_1") (pintype "passive"))
      (node (ref "C234") (pin "1") (pinfunction "1_1") (pintype "passive"))
      (node (ref "C235") (pin "2") (pinfunction "2_2") (pintype "passive"))
      (node (ref "C236") (pin "2") (pinfunction "2_2") (pintype "passive"))
      (node (ref "C237") (pin "2") (pinfunction "2_2") (pintype "passive"))
      (node (ref "C238") (pin "2") (pinfunction "2_2") (pintype "passive"))
      (node (ref "C239") (pin "1") (pinfunction "1_1") (pintype "passive"))
      (node (ref "C247") (pin "2") (pinfunction "2_2") (pintype "passive"))
      (node (ref "C249") (pin "1") (pinfunction "1_1") (pintype "passive"))
      (node (ref "C250") (pin "2") (pinfunction "2_2") (pintype "passive"))
      (node (ref "C251") (pin "2") (pinfunction "2_2") (pintype "passive"))
      (node (ref "C252") (pin "2") (pinfunction "2_2") (pintype "passive"))
      (node (ref "C253") (pin "2") (pinfunction "2_2") (pintype "passive"))
      (node (ref "C254") (pin "1") (pinfunction "1_1") (pintype "passive"))
      (node (ref "C255") (pin "1") (pinfunction "1_1") (pintype "passive"))
      (node (ref "C256") (pin "1") (pinfunction "1_1") (pintype "passive"))
      (node (ref "C257") (pin "1") (pinfunction "1_1") (pintype "passive"))
      (node (ref "C258") (pin "2") (pinfunction "2_2") (pintype "passive"))
      (node (ref "C259") (pin "2") (pinfunction "2_2") (pintype "passive"))
      (node (ref "C260") (pin "2") (pinfunction "2_2") (pintype "passive"))
      (node (ref "C261") (pin "2") (pinfunction "2_2") (pintype "passive"))
      (node (ref "J66") (pin "2") (pinfunction "2_2") (pintype "passive"))
      (node (ref "J66") (pin "3") (pinfunction "3_3") (pintype "passive"))
      (node (ref "J66") (pin "4") (pinfunction "4_4") (pintype "passive"))
      (node (ref "J66") (pin "5") (pinfunction "5_5") (pintype "passive"))
      (node (ref "J67") (pin "1") (pinfunction "SLEEVE_1") (pintype "passive"))
      (node (ref "J68") (pin "2") (pinfunction "2_2") (pintype "passive"))
      (node (ref "J68") (pin "3") (pinfunction "3_3") (pintype "passive"))
      (node (ref "J68") (pin "4") (pinfunction "4_4") (pintype "passive"))
      (node (ref "J68") (pin "5") (pinfunction "5_5") (pintype "passive"))
      (node (ref "R166") (pin "2") (pinfunction "2_2") (pintype "passive"))
      (node (ref "R173") (pin "2") (pinfunction "2_2") (pintype "passive"))
      (node (ref "R176") (pin "2") (pinfunction "2_2") (pintype "passive"))
      (node (ref "R178") (pin "2") (pinfunction "2_2") (pintype "passive"))
      (node (ref "TP69") (pin "1") (pintype "passive"))
      (node (ref "U15") (pin "9") (pinfunction "EP_9") (pintype "passive"))
      (node (ref "U16") (pin "9") (pinfunction "EP_9") (pintype "passive"))
    )
    (net (code "14") (name "Net-(C223-Pad1)") (class "Default")
      (node (ref "C223") (pin "1") (pinfunction "1_1") (pintype "passive"))
      (node (ref "R143") (pin "1") (pinfunction "1_1") (pintype "passive"))
    )
    (net (code "15") (name "Net-(C224-Pad2)") (class "Default")
      (node (ref "C224") (pin "2") (pinfunction "2_2") (pintype "passive"))
      (node (ref "R144") (pin "2") (pinfunction "2_2") (pintype "passive"))
    )
    (net (code "16") (name "Net-(C225-Pad1)") (class "Default")
      (node (ref "C225") (pin "1") (pinfunction "1_1") (pintype "passive"))
      (node (ref "R145") (pin "1") (pinfunction "1_1") (pintype "passive"))
    )
    (net (code "17") (name "Net-(C242-Pad1)") (class "Default")
      (node (ref "C242") (pin "1") (pinfunction "1_1") (pintype "passive"))
      (node (ref "R152") (pin "1") (pinfunction "1_1") (pintype "passive"))
    )
    (net (code "18") (name "Net-(C243-Pad2)") (class "Default")
      (node (ref "C243") (pin "2") (pinfunction "2_2") (pintype "passive"))
      (node (ref "R153") (pin "2") (pinfunction "2_2") (pintype "passive"))
    )
    (net (code "19") (name "Net-(C244-Pad1)") (class "Default")
      (node (ref "C244") (pin "1") (pinfunction "1_1") (pintype "passive"))
      (node (ref "R154") (pin "1") (pinfunction "1_1") (pintype "passive"))
    )
    (net (code "20") (name "Net-(U15-VIN+)") (class "Default")
      (node (ref "C221") (pin "2") (pinfunction "2_2") (pintype "passive"))
      (node (ref "R141") (pin "1") (pinfunction "1_1") (pintype "passive"))
      (node (ref "R158") (pin "1") (pinfunction "1_1") (pintype "passive"))
      (node (ref "U15") (pin "8") (pinfunction "VIN+_8") (pintype "input"))
    )
    (net (code "21") (name "Net-(U15-VIN-)") (class "Default")
      (node (ref "C228") (pin "2") (pinfunction "2_2") (pintype "passive"))
      (node (ref "R147") (pin "1") (pinfunction "1_1") (pintype "passive"))
      (node (ref "R159") (pin "1") (pinfunction "1_1") (pintype "passive"))
      (node (ref "U15") (pin "1") (pinfunction "VIN-_1") (pintype "input"))
    )
    (net (code "22") (name "Net-(U15-VOUT+)") (class "Default")
      (node (ref "C225") (pin "2") (pinfunction "2_2") (pintype "passive"))
      (node (ref "C228") (pin "1") (pinfunction "1_1") (pintype "passive"))
      (node (ref "R147") (pin "2") (pinfunction "2_2") (pintype "passive"))
      (node (ref "U15") (pin "4") (pinfunction "VOUT+_4") (pintype "output"))
    )
    (net (code "23") (name "Net-(U15-VOUT-)") (class "Default")
      (node (ref "C221") (pin "1") (pinfunction "1_1") (pintype "passive"))
      (node (ref "C223") (pin "2") (pinfunction "2_2") (pintype "passive"))
      (node (ref "R141") (pin "2") (pinfunction "2_2") (pintype "passive"))
      (node (ref "U15") (pin "5") (pinfunction "VOUT-_5") (pintype "output"))
    )
    (net (code "24") (name "Net-(U16-VIN+)") (class "Default")
      (node (ref "C240") (pin "2") (pinfunction "2_2") (pintype "passive"))
      (node (ref "R150") (pin "1") (pinfunction "1_1") (pintype "passive"))
      (node (ref "R164") (pin "1") (pinfunction "1_1") (pintype "passive"))
      (node (ref "U16") (pin "8") (pinfunction "VIN+_8") (pintype "input"))
    )
    (net (code "25") (name "Net-(U16-VIN-)") (class "Default")
      (node (ref "C246") (pin "2") (pinfunction "2_2") (pintype "passive"))
      (node (ref "R156") (pin "1") (pinfunction "1_1") (pintype "passive"))
      (node (ref "R167") (pin "1") (pinfunction "1_1") (pintype "passive"))
      (node (ref "U16") (pin "1") (pinfunction "VIN-_1") (pintype "input"))
    )
    (net (code "26") (name "Net-(U16-VOUT+)") (class "Default")
      (node (ref "C244") (pin "2") (pinfunction "2_2") (pintype "passive"))
      (node (ref "C246") (pin "1") (pinfunction "1_1") (pintype "passive"))
      (node (ref "R156") (pin "2") (pinfunction "2_2") (pintype "passive"))
      (node (ref "U16") (pin "4") (pinfunction "VOUT+_4") (pintype "output"))
    )
    (net (code "27") (name "Net-(U16-VOUT-)") (class "Default")
      (node (ref "C240") (pin "1") (pinfunction "1_1") (pintype "passive"))
      (node (ref "C242") (pin "2") (pinfunction "2_2") (pintype "passive"))
      (node (ref "R150") (pin "2") (pinfunction "2_2") (pintype "passive"))
      (node (ref "U16") (pin "5") (pinfunction "VOUT-_5") (pintype "output"))
    )
    (net (code "28") (name "Net-(U17A-IN_A+)") (class "Default")
      (node (ref "C245") (pin "2") (pinfunction "2_2") (pintype "passive"))
      (node (ref "R154") (pin "2") (pinfunction "2_2") (pintype "passive"))
      (node (ref "R155") (pin "1") (pinfunction "1_1") (pintype "passive"))
      (node (ref "U17") (pin "3") (pinfunction "IN_A+_3") (pintype "input"))
    )
    (net (code "29") (name "Net-(U17A-IN_A-)") (class "Default")
      (node (ref "C241") (pin "2") (pinfunction "2_2") (pintype "passive"))
      (node (ref "R151") (pin "2") (pinfunction "2_2") (pintype "passive"))
      (node (ref "R152") (pin "2") (pinfunction "2_2") (pintype "passive"))
      (node (ref "U17") (pin "2") (pinfunction "IN_A-_2") (pintype "input"))
    )
    (net (code "30") (name "Net-(U17A-OUT_A)") (class "Default")
      (node (ref "C241") (pin "1") (pinfunction "1_1") (pintype "passive"))
      (node (ref "R151") (pin "1") (pinfunction "1_1") (pintype "passive"))
      (node (ref "R153") (pin "1") (pinfunction "1_1") (pintype "passive"))
      (node (ref "U17") (pin "1") (pinfunction "OUT_A_1") (pintype "output"))
    )
    (net (code "31") (name "Net-(U17B-IN_B+)") (class "Default")
      (node (ref "C226") (pin "2") (pinfunction "2_2") (pintype "passive"))
      (node (ref "R145") (pin "2") (pinfunction "2_2") (pintype "passive"))
      (node (ref "R146") (pin "1") (pinfunction "1_1") (pintype "passive"))
      (node (ref "U17") (pin "5") (pinfunction "IN_B+_5") (pintype "input"))
    )
    (net (code "32") (name "Net-(U17B-IN_B-)") (class "Default")
      (node (ref "C222") (pin "1") (pinfunction "1_1") (pintype "passive"))
      (node (ref "R142") (pin "2") (pinfunction "2_2") (pintype "passive"))
      (node (ref "R143") (pin "2") (pinfunction "2_2") (pintype "passive"))
      (node (ref "U17") (pin "6") (pinfunction "IN_B-_6") (pintype "input"))
    )
    (net (code "33") (name "Net-(U17B-OUT_B)") (class "Default")
      (node (ref "C222") (pin "2") (pinfunction "2_2") (pintype "passive"))
      (node (ref "R142") (pin "1") (pinfunction "1_1") (pintype "passive"))
      (node (ref "R144") (pin "1") (pinfunction "1_1") (pintype "passive"))
      (node (ref "U17") (pin "7") (pinfunction "OUT_B_7") (pintype "output"))
    )
    (net (code "34") (name "Net-(U18A-IN_A+)") (class "Default")
      (node (ref "C249") (pin "2") (pinfunction "2_2") (pintype "passive"))
      (node (ref "R161") (pin "1") (pinfunction "1_1") (pintype "passive"))
      (node (ref "R162") (pin "2") (pinfunction "2_2") (pintype "passive"))
      (node (ref "U18") (pin "3") (pinfunction "IN_A+_3") (pintype "input"))
    )
    (net (code "35") (name "Net-(U18A-IN_A-)") (class "Default")
      (node (ref "C179") (pin "1") (pinfunction "1_1") (pintype "passive"))
      (node (ref "C226") (pin "1") (pinfunction "1_1") (pintype "passive"))
      (node (ref "R146") (pin "2") (pinfunction "2_2") (pintype "passive"))
      (node (ref "U18") (pin "1") (pinfunction "OUT_A_1") (pintype "output"))
      (node (ref "U18") (pin "2") (pinfunction "IN_A-_2") (pintype "input"))
    )
    (net (code "36") (name "Net-(U18B-IN_B+)") (class "Default")
      (node (ref "C173") (pin "2") (pinfunction "2_2") (pintype "passive"))
      (node (ref "R169") (pin "1") (pinfunction "1_1") (pintype "passive"))
      (node (ref "R170") (pin "2") (pinfunction "2_2") (pintype "passive"))
      (node (ref "U18") (pin "5") (pinfunction "IN_B+_5") (pintype "input"))
    )
    (net (code "37") (name "Net-(U18B-IN_B-)") (class "Default")
      (node (ref "C180") (pin "1") (pinfunction "1_1") (pintype "passive"))
      (node (ref "C245") (pin "1") (pinfunction "1_1") (pintype "passive"))
      (node (ref "R155") (pin "2") (pinfunction "2_2") (pintype "passive"))
      (node (ref "U18") (pin "6") (pinfunction "IN_B-_6") (pintype "input"))
      (node (ref "U18") (pin "7") (pinfunction "OUT_B_7") (pintype "output"))
    )
    (net (code "38") (name "Net-(U19A-IN_A-)") (class "Default")
      (node (ref "R175") (pin "2") (pinfunction "2_2") (pintype "passive"))
      (node (ref "U19") (pin "1") (pinfunction "OUT_A_1") (pintype "output"))
      (node (ref "U19") (pin "2") (pinfunction "IN_A-_2") (pintype "input"))
    )
    (net (code "39") (name "Net-(U19B-IN_B-)") (class "Default")
      (node (ref "R177") (pin "2") (pinfunction "2_2") (pintype "passive"))
      (node (ref "U19") (pin "6") (pinfunction "IN_B-_6") (pintype "input"))
      (node (ref "U19") (pin "7") (pinfunction "OUT_B_7") (pintype "output"))
    )
    (net (code "40") (name "Net-(U20A-IN_A-)") (class "Default")
      (node (ref "R165") (pin "2") (pinfunction "2_2") (pintype "passive"))
      (node (ref "U20") (pin "1") (pinfunction "OUT_A_1") (pintype "output"))
      (node (ref "U20") (pin "2") (pinfunction "IN_A-_2") (pintype "input"))
    )
    (net (code "41") (name "Net-(U20B-IN_B-)") (class "Default")
      (node (ref "R172") (pin "2") (pinfunction "2_2") (pintype "passive"))
      (node (ref "U20") (pin "6") (pinfunction "IN_B-_6") (pintype "input"))
      (node (ref "U20") (pin "7") (pinfunction "OUT_B_7") (pintype "output"))
    )
    (net (code "42") (name "OPAMP+") (class "Default")
      (node (ref "C232") (pin "1") (pinfunction "1_1") (pintype "passive"))
      (node (ref "C233") (pin "2") (pinfunction "2_2") (pintype "passive"))
      (node (ref "C234") (pin "2") (pinfunction "2_2") (pintype "passive"))
      (node (ref "C237") (pin "1") (pinfunction "1_1") (pintype "passive"))
      (node (ref "C238") (pin "1") (pinfunction "1_1") (pintype "passive"))
      (node (ref "C250") (pin "1") (pinfunction "1_1") (pintype "passive"))
      (node (ref "C251") (pin "1") (pinfunction "1_1") (pintype "passive"))
      (node (ref "C252") (pin "1") (pinfunction "1_1") (pintype "passive"))
      (node (ref "C253") (pin "1") (pinfunction "1_1") (pintype "passive"))
      (node (ref "R148") (pin "2") (pinfunction "2_2") (pintype "passive"))
      (node (ref "R161") (pin "2") (pinfunction "2_2") (pintype "passive"))
      (node (ref "R169") (pin "2") (pinfunction "2_2") (pintype "passive"))
      (node (ref "R171") (pin "2") (pinfunction "2_2") (pintype "passive"))
      (node (ref "TP68") (pin "1") (pintype "passive"))
      (node (ref "U15") (pin "3") (pinfunction "VCC+_3") (pintype "power_in"))
      (node (ref "U16") (pin "3") (pinfunction "VCC+_3") (pintype "power_in"))
      (node (ref "U17") (pin "8") (pinfunction "VS+_8") (pintype "power_in"))
      (node (ref "U18") (pin "8") (pinfunction "VS+_8") (pintype "power_in"))
      (node (ref "U19") (pin "8") (pinfunction "VS+_8") (pintype "power_in"))
      (node (ref "U20") (pin "8") (pinfunction "VS+_8") (pintype "power_in"))
    )
    (net (code "43") (name "OPAMP-") (class "Default")
      (node (ref "C229") (pin "2") (pinfunction "2_2") (pintype "passive"))
      (node (ref "C230") (pin "2") (pinfunction "2_2") (pintype "passive"))
      (node (ref "C231") (pin "1") (pinfunction "1_1") (pintype "passive"))
      (node (ref "C235") (pin "1") (pinfunction "1_1") (pintype "passive"))
      (node (ref "C236") (pin "1") (pinfunction "1_1") (pintype "passive"))
      (node (ref "C254") (pin "2") (pinfunction "2_2") (pintype "passive"))
      (node (ref "C255") (pin "2") (pinfunction "2_2") (pintype "passive"))
      (node (ref "C256") (pin "2") (pinfunction "2_2") (pintype "passive"))
      (node (ref "C257") (pin "2") (pinfunction "2_2") (pintype "passive"))
      (node (ref "R149") (pin "1") (pinfunction "1_1") (pintype "passive"))
      (node (ref "R162") (pin "1") (pinfunction "1_1") (pintype "passive"))
      (node (ref "R170") (pin "1") (pinfunction "1_1") (pintype "passive"))
      (node (ref "R174") (pin "1") (pinfunction "1_1") (pintype "passive"))
      (node (ref "TP67") (pin "1") (pintype "passive"))
      (node (ref "U15") (pin "6") (pinfunction "VCC-_6") (pintype "power_in"))
      (node (ref "U16") (pin "6") (pinfunction "VCC-_6") (pintype "power_in"))
      (node (ref "U17") (pin "4") (pinfunction "VS-_4") (pintype "power_in"))
      (node (ref "U18") (pin "4") (pinfunction "VS-_4") (pintype "power_in"))
      (node (ref "U19") (pin "4") (pinfunction "VS-_4") (pintype "power_in"))
      (node (ref "U20") (pin "4") (pinfunction "VS-_4") (pintype "power_in"))
    )
    (net (code "44") (name "unconnected-(U15-NC-Pad7)") (class "Default")
      (node (ref "U15") (pin "7") (pinfunction "NC_7") (pintype "passive+no_connect"))
    )
    (net (code "45") (name "unconnected-(U16-NC-Pad7)") (class "Default")
      (node (ref "U16") (pin "7") (pinfunction "NC_7") (pintype "passive+no_connect"))
    )
  )
)
